# Sensors.net
KiCad netlist of a schematic drawn in Altium Designer
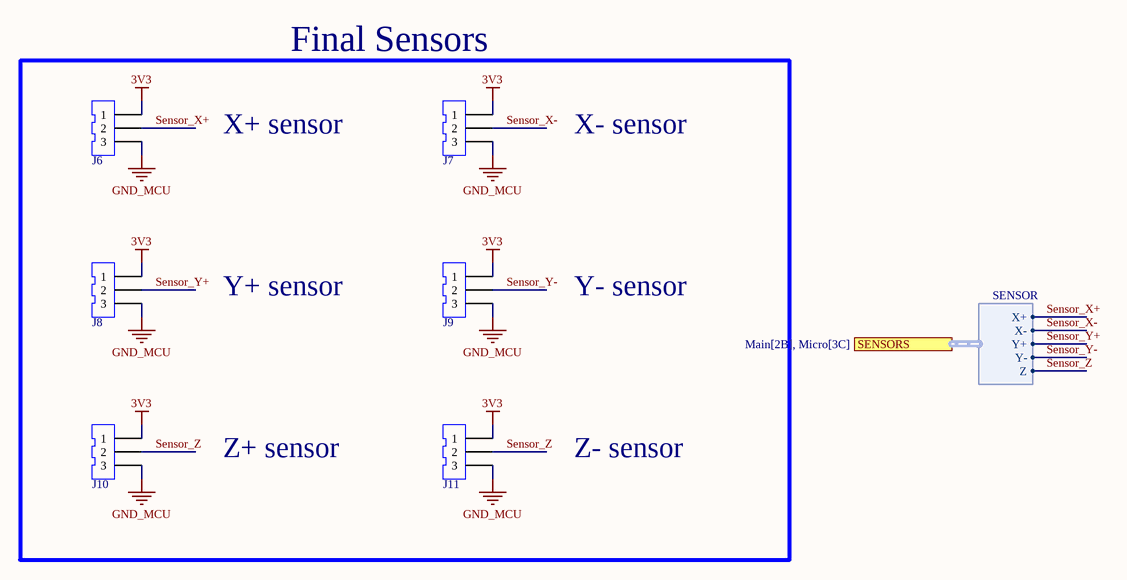
[diagram p0: Sensors.SchDoc]

(export (version "E")
  (design (tool "Eeschema 10.0.6"))
  (components
    (comp (ref "J6")
      (value "CONN HEADER TH 3POS 2.5mm")
      (footprint "JST_B3B-XH-A")
      (fields
        (field (name "MANUFACTURER") "JST")
        (field (name "MANUFACTURER PART NUMBER") "B3B-XH-A(LF)(SN)")
      )
      (libsource (lib "CNCLib") (part "Connector JST 3pin"))
    )
    (comp (ref "J7")
      (value "CONN HEADER TH 3POS 2.5mm")
      (footprint "JST_B3B-XH-A")
      (fields
        (field (name "MANUFACTURER") "JST")
        (field (name "MANUFACTURER PART NUMBER") "B3B-XH-A(LF)(SN)")
      )
      (libsource (lib "CNCLib") (part "Connector JST 3pin"))
    )
    (comp (ref "J8")
      (value "CONN HEADER TH 3POS 2.5mm")
      (footprint "JST_B3B-XH-A")
      (fields
        (field (name "MANUFACTURER") "JST")
        (field (name "MANUFACTURER PART NUMBER") "B3B-XH-A(LF)(SN)")
      )
      (libsource (lib "CNCLib") (part "Connector JST 3pin"))
    )
    (comp (ref "J9")
      (value "CONN HEADER TH 3POS 2.5mm")
      (footprint "JST_B3B-XH-A")
      (fields
        (field (name "MANUFACTURER") "JST")
        (field (name "MANUFACTURER PART NUMBER") "B3B-XH-A(LF)(SN)")
      )
      (libsource (lib "CNCLib") (part "Connector JST 3pin"))
    )
    (comp (ref "J10")
      (value "CONN HEADER TH 3POS 2.5mm")
      (footprint "JST_B3B-XH-A")
      (fields
        (field (name "MANUFACTURER") "JST")
        (field (name "MANUFACTURER PART NUMBER") "B3B-XH-A(LF)(SN)")
      )
      (libsource (lib "CNCLib") (part "Connector JST 3pin"))
    )
    (comp (ref "J11")
      (value "CONN HEADER TH 3POS 2.5mm")
      (footprint "JST_B3B-XH-A")
      (fields
        (field (name "MANUFACTURER") "JST")
        (field (name "MANUFACTURER PART NUMBER") "B3B-XH-A(LF)(SN)")
      )
      (libsource (lib "CNCLib") (part "Connector JST 3pin"))
    )
  )
  (nets
    (net (code "2") (name "/Sensor_X+") (class "Default")
      (node (ref "J6") (pin "2") (pinfunction "2_2") (pintype "passive"))
    )
    (net (code "3") (name "/Sensor_X-") (class "Default")
      (node (ref "J7") (pin "2") (pinfunction "2_2") (pintype "passive"))
    )
    (net (code "4") (name "/Sensor_Y+") (class "Default")
      (node (ref "J8") (pin "2") (pinfunction "2_2") (pintype "passive"))
    )
    (net (code "5") (name "/Sensor_Y-") (class "Default")
      (node (ref "J9") (pin "2") (pinfunction "2_2") (pintype "passive"))
    )
    (net (code "6") (name "/Sensor_Z") (class "Default")
      (node (ref "J10") (pin "2") (pinfunction "2_2") (pintype "passive"))
      (node (ref "J11") (pin "2") (pinfunction "2_2") (pintype "passive"))
    )
    (net (code "8") (name "3V3") (class "Default")
      (node (ref "J10") (pin "1") (pinfunction "1_1") (pintype "passive"))
      (node (ref "J11") (pin "1") (pinfunction "1_1") (pintype "passive"))
      (node (ref "J6") (pin "1") (pinfunction "1_1") (pintype "passive"))
      (node (ref "J7") (pin "1") (pinfunction "1_1") (pintype "passive"))
      (node (ref "J8") (pin "1") (pinfunction "1_1") (pintype "passive"))
      (node (ref "J9") (pin "1") (pinfunction "1_1") (pintype "passive"))
    )
    (net (code "9") (name "GND_MCU") (class "Default")
      (node (ref "J10") (pin "3") (pinfunction "3_3") (pintype "passive"))
      (node (ref "J11") (pin "3") (pinfunction "3_3") (pintype "passive"))
      (node (ref "J6") (pin "3") (pinfunction "3_3") (pintype "passive"))
      (node (ref "J7") (pin "3") (pinfunction "3_3") (pintype "passive"))
      (node (ref "J8") (pin "3") (pinfunction "3_3") (pintype "passive"))
      (node (ref "J9") (pin "3") (pinfunction "3_3") (pintype "passive"))
    )
  )
)
